# x0x-heart-power.net
KiCad netlist of a schematic drawn in EAGLE
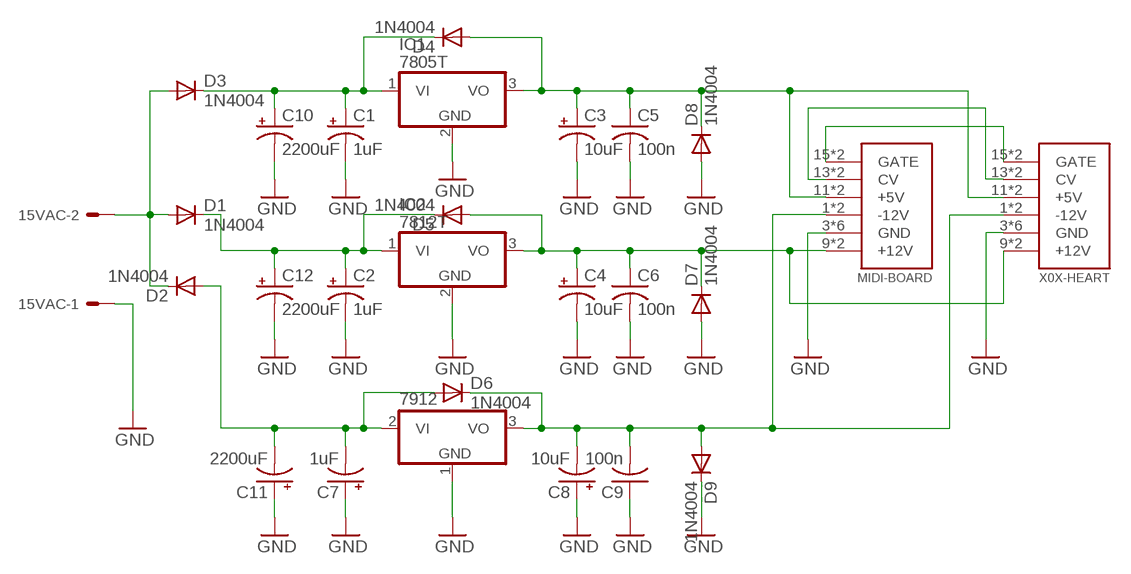
[diagram p0: schematic, sheet 1]

(export (version "E")
  (design (tool "Eeschema 10.0.6"))
  (components
    (comp (ref "15VAC")
      (value "KK-156-2")
      (footprint "eagle-import:KK-156-2")
      (libsource (lib "eagle-import") (part "KK-156-2"))
    )
    (comp (ref "7912")
      (value "7912T")
      (footprint "eagle-import:TO220H")
      (libsource (lib "eagle-import") (part "79T12"))
    )
    (comp (ref "C1")
      (value "1uF")
      (footprint "eagle-import:E2-5")
      (libsource (lib "eagle-import") (part "CPOL-USE2-5"))
    )
    (comp (ref "C2")
      (value "1uF")
      (footprint "eagle-import:E2-5")
      (libsource (lib "eagle-import") (part "CPOL-USE2-5"))
    )
    (comp (ref "C3")
      (value "10uF")
      (footprint "eagle-import:E2-5")
      (libsource (lib "eagle-import") (part "CPOL-USE2-5"))
    )
    (comp (ref "C4")
      (value "10uF")
      (footprint "eagle-import:E2-5")
      (libsource (lib "eagle-import") (part "CPOL-USE2-5"))
    )
    (comp (ref "C5")
      (value "100n")
      (footprint "eagle-import:C025-024X044")
      (libsource (lib "eagle-import") (part "C-US025-024X044"))
    )
    (comp (ref "C6")
      (value "100n")
      (footprint "eagle-import:C025-024X044")
      (libsource (lib "eagle-import") (part "C-US025-024X044"))
    )
    (comp (ref "C7")
      (value "1uF")
      (footprint "eagle-import:E2-5")
      (libsource (lib "eagle-import") (part "CPOL-USE2-5"))
    )
    (comp (ref "C8")
      (value "10uF")
      (footprint "eagle-import:E2-5")
      (libsource (lib "eagle-import") (part "CPOL-USE2-5"))
    )
    (comp (ref "C9")
      (value "100n")
      (footprint "eagle-import:C025-024X044")
      (libsource (lib "eagle-import") (part "C-US025-024X044"))
    )
    (comp (ref "C10")
      (value "2200uF")
      (footprint "eagle-import:E22-6")
      (libsource (lib "eagle-import") (part "CPOL-USE22-6AXIAL"))
    )
    (comp (ref "C11")
      (value "2200uF")
      (footprint "eagle-import:E22-6")
      (libsource (lib "eagle-import") (part "CPOL-USE22-6AXIAL"))
    )
    (comp (ref "C12")
      (value "2200uF")
      (footprint "eagle-import:E22-6")
      (libsource (lib "eagle-import") (part "CPOL-USE22-6AXIAL"))
    )
    (comp (ref "D1")
      (value "1N4004")
      (footprint "eagle-import:DO41-10")
      (libsource (lib "eagle-import") (part "1N4004"))
    )
    (comp (ref "D2")
      (value "1N4004")
      (footprint "eagle-import:DO41-10")
      (libsource (lib "eagle-import") (part "1N4004"))
    )
    (comp (ref "D3")
      (value "1N4004")
      (footprint "eagle-import:DO41-10")
      (libsource (lib "eagle-import") (part "1N4004"))
    )
    (comp (ref "D4")
      (value "1N4004")
      (footprint "eagle-import:DO41-10")
      (libsource (lib "eagle-import") (part "1N4004"))
    )
    (comp (ref "D5")
      (value "1N4004")
      (footprint "eagle-import:DO41-10")
      (libsource (lib "eagle-import") (part "1N4004"))
    )
    (comp (ref "D6")
      (value "1N4004")
      (footprint "eagle-import:DO41-10")
      (libsource (lib "eagle-import") (part "1N4004"))
    )
    (comp (ref "D7")
      (value "1N4004")
      (footprint "eagle-import:DO41-10")
      (libsource (lib "eagle-import") (part "1N4004"))
    )
    (comp (ref "D8")
      (value "1N4004")
      (footprint "eagle-import:DO41-10")
      (libsource (lib "eagle-import") (part "1N4004"))
    )
    (comp (ref "D9")
      (value "1N4004")
      (footprint "eagle-import:DO41-10")
      (libsource (lib "eagle-import") (part "1N4004"))
    )
    (comp (ref "IC1")
      (value "7805T")
      (footprint "eagle-import:TO220H")
      (libsource (lib "eagle-import") (part "78T05"))
    )
    (comp (ref "IC2")
      (value "7812T")
      (footprint "eagle-import:TO220H")
      (libsource (lib "eagle-import") (part "78T12"))
    )
    (comp (ref "MIDI-BOARD")
      (value "POWER")
      (footprint "eagle-import:POWER_16")
      (libsource (lib "eagle-import") (part "POWER"))
    )
    (comp (ref "X0X-HEART")
      (value "POWER")
      (footprint "eagle-import:POWER_16")
      (libsource (lib "eagle-import") (part "POWER"))
    )
  )
  (nets
    (net (code "1") (name "GND") (class "Default")
      (node (ref "15VAC") (pin "1") (pinfunction "S_1") (pintype "passive"))
      (node (ref "7912") (pin "1") (pinfunction "GND_1") (pintype "passive"))
      (node (ref "C1") (pin "-") (pinfunction "-_-") (pintype "passive"))
      (node (ref "C10") (pin "-") (pinfunction "-_-") (pintype "passive"))
      (node (ref "C11") (pin "+") (pinfunction "+_+") (pintype "passive"))
      (node (ref "C12") (pin "-") (pinfunction "-_-") (pintype "passive"))
      (node (ref "C2") (pin "-") (pinfunction "-_-") (pintype "passive"))
      (node (ref "C3") (pin "-") (pinfunction "-_-") (pintype "passive"))
      (node (ref "C4") (pin "-") (pinfunction "-_-") (pintype "passive"))
      (node (ref "C5") (pin "2") (pinfunction "2_2") (pintype "passive"))
      (node (ref "C6") (pin "2") (pinfunction "2_2") (pintype "passive"))
      (node (ref "C7") (pin "+") (pinfunction "+_+") (pintype "passive"))
      (node (ref "C8") (pin "+") (pinfunction "+_+") (pintype "passive"))
      (node (ref "C9") (pin "1") (pinfunction "1_1") (pintype "passive"))
      (node (ref "D7") (pin "A") (pinfunction "A_A") (pintype "passive"))
      (node (ref "D8") (pin "A") (pinfunction "A_A") (pintype "passive"))
      (node (ref "D9") (pin "C") (pinfunction "C_C") (pintype "passive"))
      (node (ref "IC1") (pin "2") (pinfunction "GND_2") (pintype "passive"))
      (node (ref "IC2") (pin "2") (pinfunction "GND_2") (pintype "passive"))
      (node (ref "MIDI-BOARD") (pin "3") (pinfunction "GND_3") (pintype "bidirectional"))
      (node (ref "MIDI-BOARD") (pin "4") (pinfunction "GND_4") (pintype "bidirectional"))
      (node (ref "MIDI-BOARD") (pin "5") (pinfunction "GND_5") (pintype "bidirectional"))
      (node (ref "MIDI-BOARD") (pin "6") (pinfunction "GND_6") (pintype "bidirectional"))
      (node (ref "MIDI-BOARD") (pin "7") (pinfunction "GND_7") (pintype "bidirectional"))
      (node (ref "MIDI-BOARD") (pin "8") (pinfunction "GND_8") (pintype "bidirectional"))
      (node (ref "X0X-HEART") (pin "3") (pinfunction "GND_3") (pintype "bidirectional"))
      (node (ref "X0X-HEART") (pin "4") (pinfunction "GND_4") (pintype "bidirectional"))
      (node (ref "X0X-HEART") (pin "5") (pinfunction "GND_5") (pintype "bidirectional"))
      (node (ref "X0X-HEART") (pin "6") (pinfunction "GND_6") (pintype "bidirectional"))
      (node (ref "X0X-HEART") (pin "7") (pinfunction "GND_7") (pintype "bidirectional"))
      (node (ref "X0X-HEART") (pin "8") (pinfunction "GND_8") (pintype "bidirectional"))
    )
    (net (code "2") (name "Net-(15VACB-S)") (class "Default")
      (node (ref "15VAC") (pin "2") (pinfunction "S_2") (pintype "passive"))
      (node (ref "D1") (pin "A") (pinfunction "A_A") (pintype "passive"))
      (node (ref "D2") (pin "C") (pinfunction "C_C") (pintype "passive"))
      (node (ref "D3") (pin "A") (pinfunction "A_A") (pintype "passive"))
    )
    (net (code "3") (name "Net-(7912-VI)") (class "Default")
      (node (ref "7912") (pin "2") (pinfunction "VI_2") (pintype "input"))
      (node (ref "C11") (pin "-") (pinfunction "-_-") (pintype "passive"))
      (node (ref "C7") (pin "-") (pinfunction "-_-") (pintype "passive"))
      (node (ref "D2") (pin "A") (pinfunction "A_A") (pintype "passive"))
      (node (ref "D6") (pin "A") (pinfunction "A_A") (pintype "passive"))
    )
    (net (code "4") (name "Net-(7912-VO)") (class "Default")
      (node (ref "7912") (pin "3") (pinfunction "VO_3") (pintype "passive"))
      (node (ref "C8") (pin "-") (pinfunction "-_-") (pintype "passive"))
      (node (ref "C9") (pin "2") (pinfunction "2_2") (pintype "passive"))
      (node (ref "D6") (pin "C") (pinfunction "C_C") (pintype "passive"))
      (node (ref "D9") (pin "A") (pinfunction "A_A") (pintype "passive"))
      (node (ref "MIDI-BOARD") (pin "1") (pinfunction "-12V_1") (pintype "bidirectional"))
      (node (ref "MIDI-BOARD") (pin "2") (pinfunction "-12V_2") (pintype "bidirectional"))
      (node (ref "X0X-HEART") (pin "1") (pinfunction "-12V_1") (pintype "bidirectional"))
      (node (ref "X0X-HEART") (pin "2") (pinfunction "-12V_2") (pintype "bidirectional"))
    )
    (net (code "5") (name "Net-(IC1-VI)") (class "Default")
      (node (ref "C1") (pin "+") (pinfunction "+_+") (pintype "passive"))
      (node (ref "C10") (pin "+") (pinfunction "+_+") (pintype "passive"))
      (node (ref "D3") (pin "C") (pinfunction "C_C") (pintype "passive"))
      (node (ref "D4") (pin "C") (pinfunction "C_C") (pintype "passive"))
      (node (ref "IC1") (pin "1") (pinfunction "VI_1") (pintype "input"))
    )
    (net (code "6") (name "Net-(IC1-VO)") (class "Default")
      (node (ref "C3") (pin "+") (pinfunction "+_+") (pintype "passive"))
      (node (ref "C5") (pin "1") (pinfunction "1_1") (pintype "passive"))
      (node (ref "D4") (pin "A") (pinfunction "A_A") (pintype "passive"))
      (node (ref "D8") (pin "C") (pinfunction "C_C") (pintype "passive"))
      (node (ref "IC1") (pin "3") (pinfunction "VO_3") (pintype "passive"))
      (node (ref "MIDI-BOARD") (pin "11") (pinfunction "+5V_11") (pintype "bidirectional"))
      (node (ref "MIDI-BOARD") (pin "12") (pinfunction "+5V_12") (pintype "bidirectional"))
      (node (ref "X0X-HEART") (pin "11") (pinfunction "+5V_11") (pintype "bidirectional"))
      (node (ref "X0X-HEART") (pin "12") (pinfunction "+5V_12") (pintype "bidirectional"))
    )
    (net (code "7") (name "Net-(IC2-VI)") (class "Default")
      (node (ref "C12") (pin "+") (pinfunction "+_+") (pintype "passive"))
      (node (ref "C2") (pin "+") (pinfunction "+_+") (pintype "passive"))
      (node (ref "D1") (pin "C") (pinfunction "C_C") (pintype "passive"))
      (node (ref "D5") (pin "C") (pinfunction "C_C") (pintype "passive"))
      (node (ref "IC2") (pin "1") (pinfunction "VI_1") (pintype "input"))
    )
    (net (code "8") (name "Net-(IC2-VO)") (class "Default")
      (node (ref "C4") (pin "+") (pinfunction "+_+") (pintype "passive"))
      (node (ref "C6") (pin "1") (pinfunction "1_1") (pintype "passive"))
      (node (ref "D5") (pin "A") (pinfunction "A_A") (pintype "passive"))
      (node (ref "D7") (pin "C") (pinfunction "C_C") (pintype "passive"))
      (node (ref "IC2") (pin "3") (pinfunction "VO_3") (pintype "passive"))
      (node (ref "MIDI-BOARD") (pin "10") (pinfunction "+12V_10") (pintype "bidirectional"))
      (node (ref "MIDI-BOARD") (pin "9") (pinfunction "+12V_9") (pintype "bidirectional"))
      (node (ref "X0X-HEART") (pin "10") (pinfunction "+12V_10") (pintype "bidirectional"))
      (node (ref "X0X-HEART") (pin "9") (pinfunction "+12V_9") (pintype "bidirectional"))
    )
    (net (code "9") (name "Net-(MIDI-BOARD-CV-Pad13)") (class "Default")
      (node (ref "MIDI-BOARD") (pin "13") (pinfunction "CV_13") (pintype "bidirectional"))
      (node (ref "MIDI-BOARD") (pin "14") (pinfunction "CV_14") (pintype "bidirectional"))
      (node (ref "X0X-HEART") (pin "13") (pinfunction "CV_13") (pintype "bidirectional"))
      (node (ref "X0X-HEART") (pin "14") (pinfunction "CV_14") (pintype "bidirectional"))
    )
    (net (code "10") (name "Net-(MIDI-BOARD-GATE-Pad15)") (class "Default")
      (node (ref "MIDI-BOARD") (pin "15") (pinfunction "GATE_15") (pintype "bidirectional"))
      (node (ref "MIDI-BOARD") (pin "16") (pinfunction "GATE_16") (pintype "bidirectional"))
      (node (ref "X0X-HEART") (pin "15") (pinfunction "GATE_15") (pintype "bidirectional"))
      (node (ref "X0X-HEART") (pin "16") (pinfunction "GATE_16") (pintype "bidirectional"))
    )
  )
)
